# INKTIME_SCHEMA.net
KiCad netlist of a schematic drawn in EAGLE
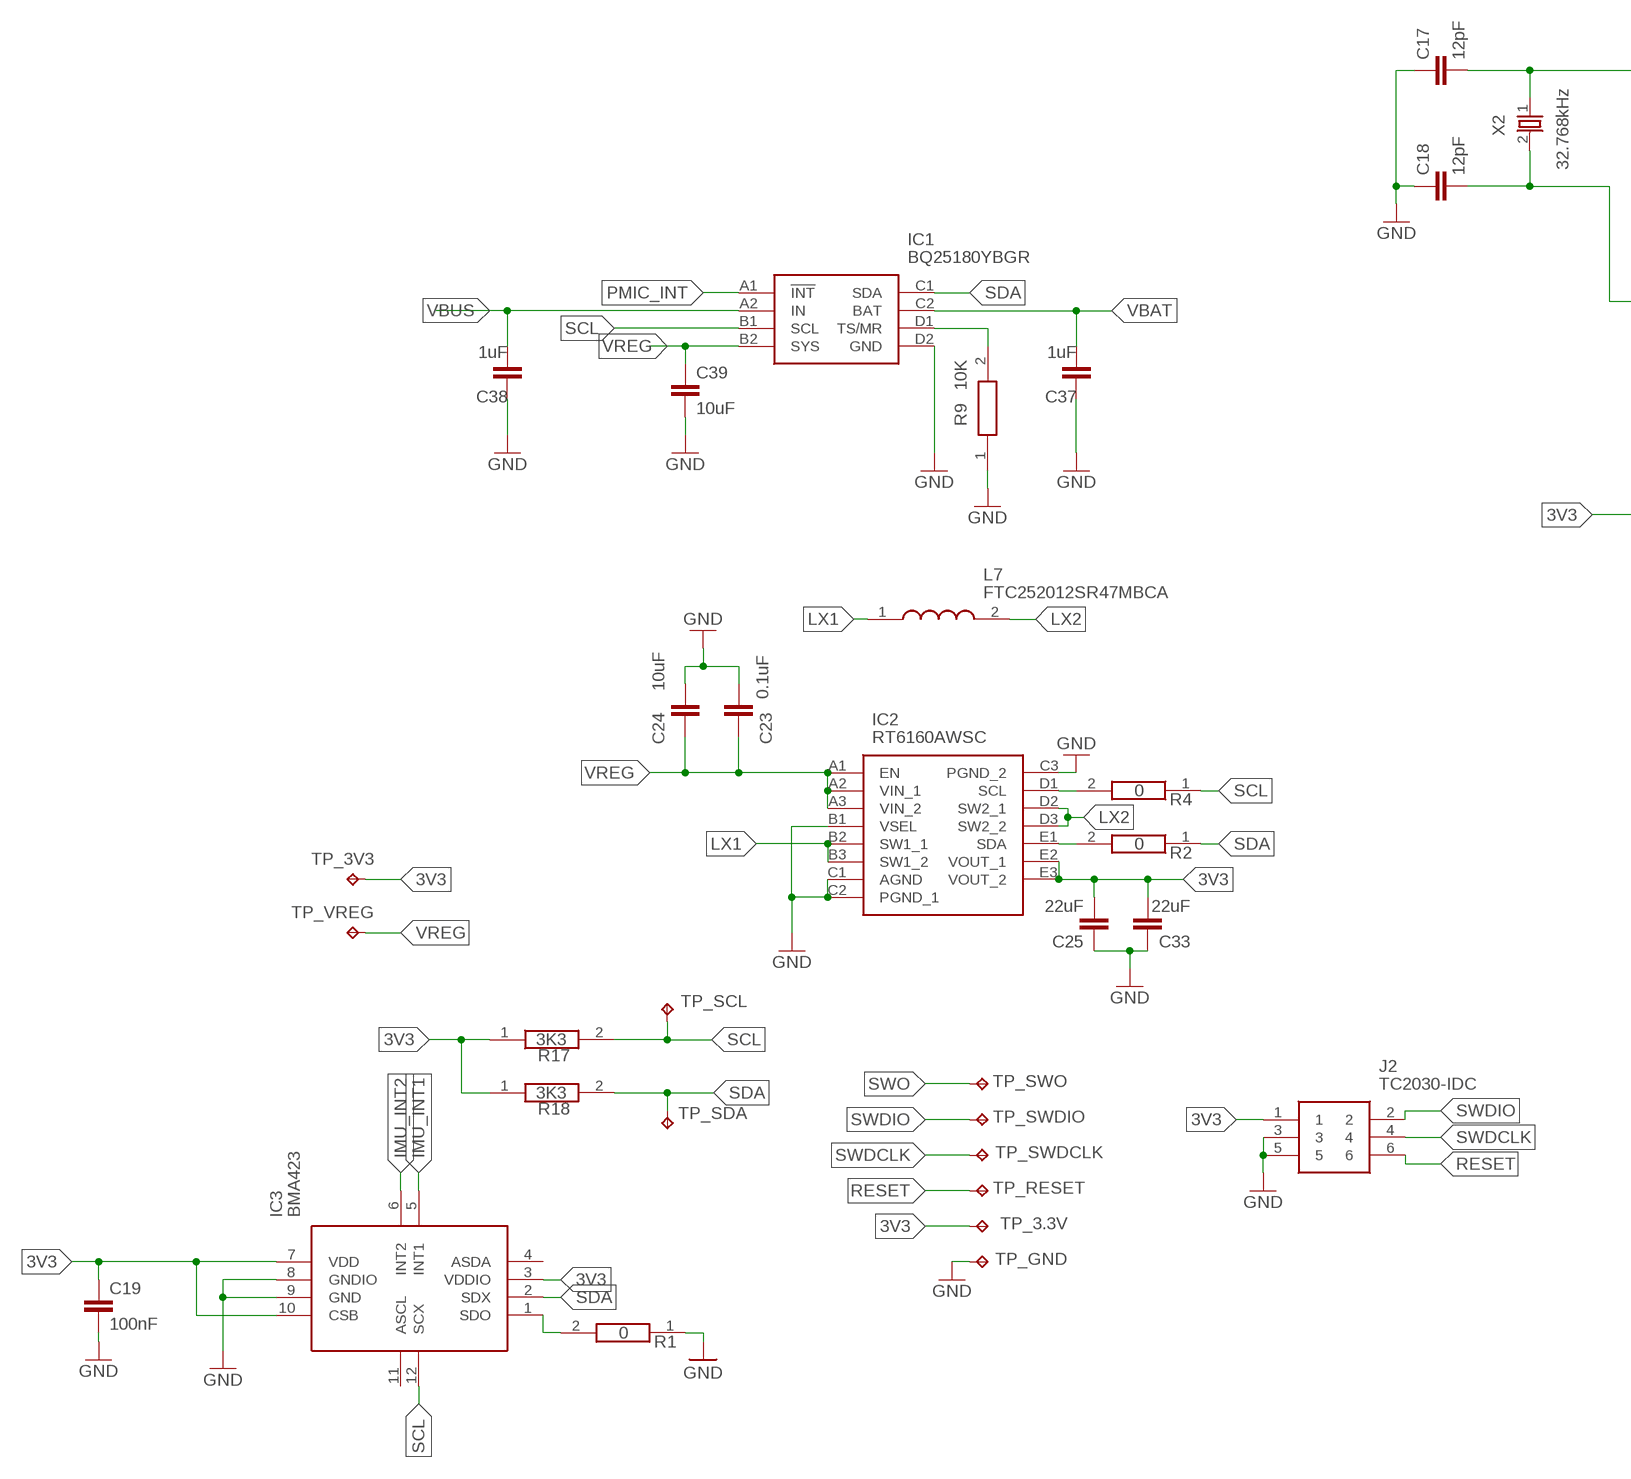
[diagram p0: schematic, sheet 1, part 1 of 2]
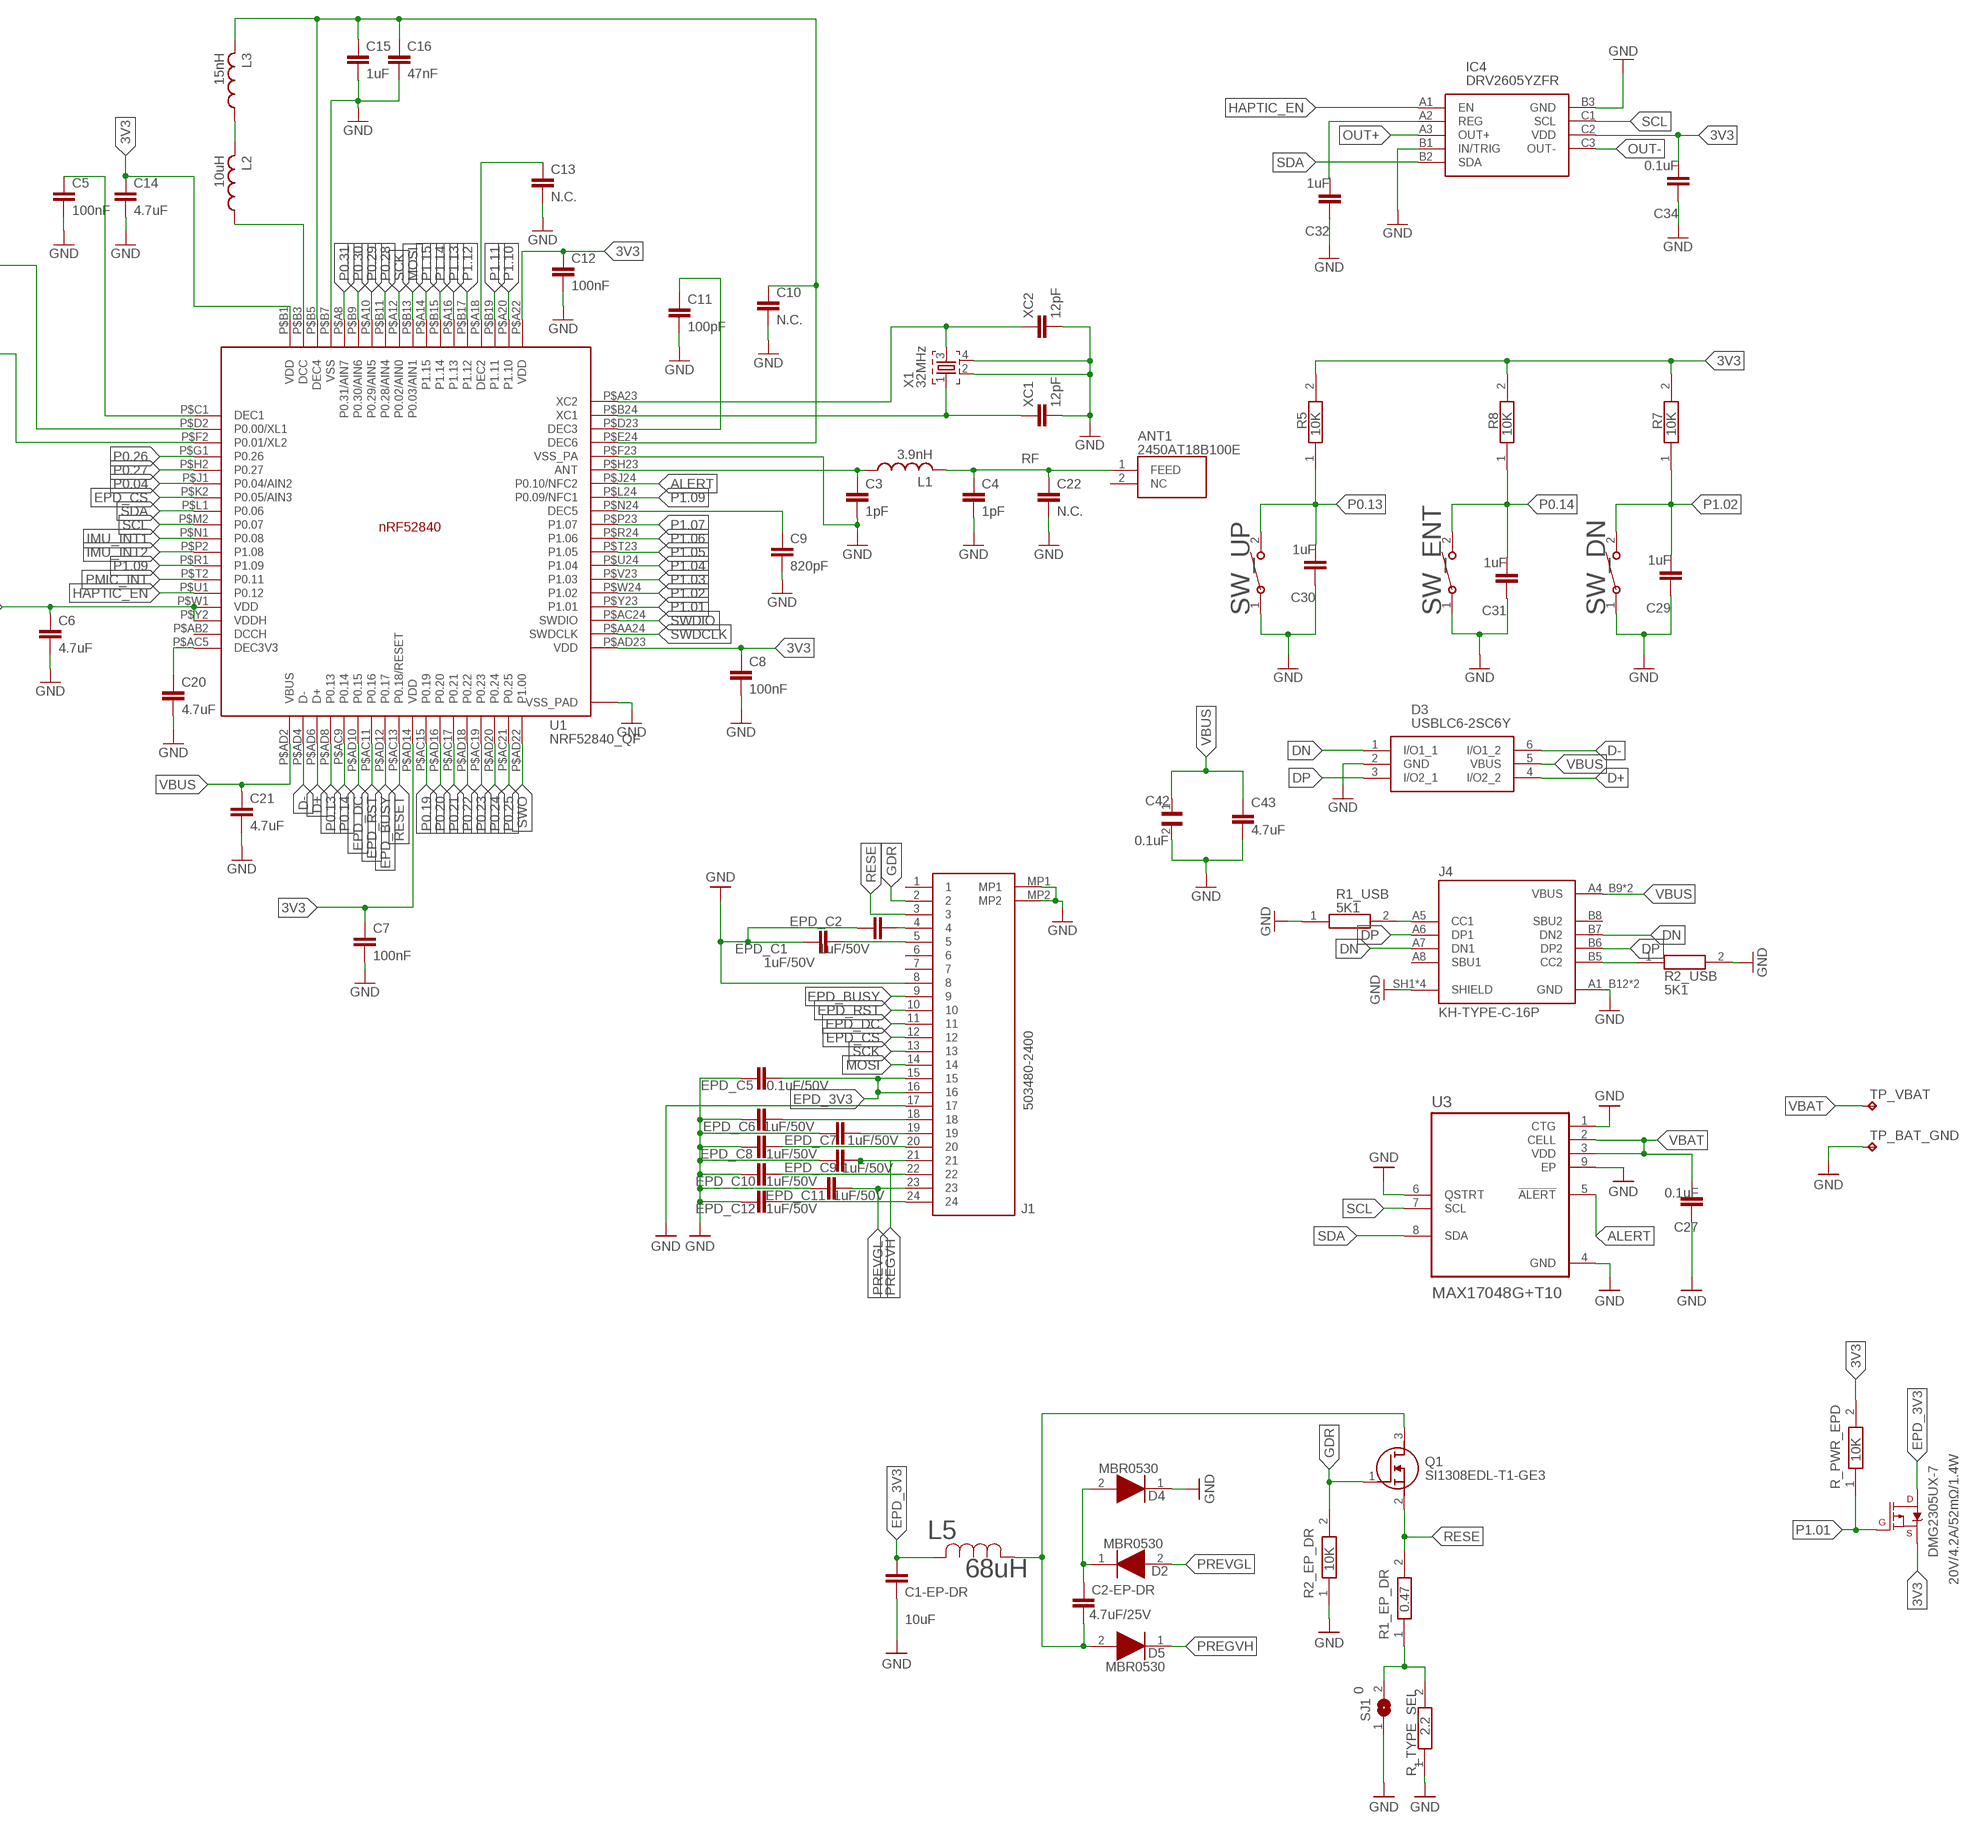
[diagram p1: schematic, sheet 1, part 2 of 2]

(export (version "E")
  (design (tool "Eeschema 10.0.6"))
  (components
    (comp (ref "ANT1")
      (value "2450AT18B100E")
      (footprint "eagle-import:2450AT18B100E_ANTC3216X140N")
      (fields (field (name "MOUSER_PART_NUMBER") "609-2450AT18B100E"))
      (libsource (lib "eagle-import") (part "2450AT18B100E_2450AT18B100E"))
    )
    (comp (ref "C1-EP-DR")
      (value "10uF")
      (footprint "eagle-import:NORDIC_NRF_3_RESC0402_L")
      (libsource (lib "eagle-import") (part "NORDIC_NRF_3_CAPACITOR_0402_L"))
    )
    (comp (ref "C2-EP-DR")
      (value "4.7uF/25V")
      (footprint "eagle-import:NORDIC_NRF_3_RESC0402_L")
      (libsource (lib "eagle-import") (part "NORDIC_NRF_3_CAPACITOR_0402_L"))
    )
    (comp (ref "C3")
      (value "1pF")
      (footprint "eagle-import:NORDIC_NRF_3_RESC0201_L")
      (libsource (lib "eagle-import") (part "NORDIC_NRF_3_CAPACITOR_0201_L"))
    )
    (comp (ref "C4")
      (value "1pF")
      (footprint "eagle-import:NORDIC_NRF_3_RESC0201_L")
      (libsource (lib "eagle-import") (part "NORDIC_NRF_3_CAPACITOR_0201_L"))
    )
    (comp (ref "C5")
      (value "100nF")
      (footprint "eagle-import:NORDIC_NRF_3_RESC0201_L")
      (libsource (lib "eagle-import") (part "NORDIC_NRF_3_CAPACITOR_0201_L"))
    )
    (comp (ref "C6")
      (value "4.7uF")
      (footprint "eagle-import:PERFECT_0402_0402")
      (libsource (lib "eagle-import") (part "PERFECT_0402_CAP_0402"))
    )
    (comp (ref "C7")
      (value "100nF")
      (footprint "eagle-import:NORDIC_NRF_3_RESC0201_L")
      (libsource (lib "eagle-import") (part "NORDIC_NRF_3_CAPACITOR_0201_L"))
    )
    (comp (ref "C8")
      (value "100nF")
      (footprint "eagle-import:NORDIC_NRF_3_RESC0201_L")
      (libsource (lib "eagle-import") (part "NORDIC_NRF_3_CAPACITOR_0201_L"))
    )
    (comp (ref "C9")
      (value "820pF")
      (footprint "eagle-import:NORDIC_NRF_3_RESC0201_L")
      (libsource (lib "eagle-import") (part "NORDIC_NRF_3_CAPACITOR_0201_L"))
    )
    (comp (ref "C10")
      (value "N.C.")
      (footprint "eagle-import:NORDIC_NRF_3_RESC0201_L")
      (libsource (lib "eagle-import") (part "NORDIC_NRF_3_CAPACITOR_0201_L"))
    )
    (comp (ref "C11")
      (value "100pF")
      (footprint "eagle-import:NORDIC_NRF_3_RESC0201_L")
      (libsource (lib "eagle-import") (part "NORDIC_NRF_3_CAPACITOR_0201_L"))
    )
    (comp (ref "C12")
      (value "100nF")
      (footprint "eagle-import:NORDIC_NRF_3_RESC0201_L")
      (libsource (lib "eagle-import") (part "NORDIC_NRF_3_CAPACITOR_0201_L"))
    )
    (comp (ref "C13")
      (value "N.C.")
      (footprint "eagle-import:NORDIC_NRF_3_RESC0201_L")
      (libsource (lib "eagle-import") (part "NORDIC_NRF_3_CAPACITOR_0201_L"))
    )
    (comp (ref "C14")
      (value "4.7uF")
      (footprint "eagle-import:PERFECT_0402_0402")
      (libsource (lib "eagle-import") (part "PERFECT_0402_CAP_0402"))
    )
    (comp (ref "C15")
      (value "1uF")
      (footprint "eagle-import:NORDIC_NRF_3_RESC0402_L")
      (libsource (lib "eagle-import") (part "NORDIC_NRF_3_CAPACITOR_0402_L"))
    )
    (comp (ref "C16")
      (value "47nF")
      (footprint "eagle-import:PERFECT_0402_0402")
      (libsource (lib "eagle-import") (part "PERFECT_0402_CAP_0402"))
    )
    (comp (ref "C17")
      (value "12pF")
      (footprint "eagle-import:NORDIC_NRF_3_RESC0201_L")
      (libsource (lib "eagle-import") (part "NORDIC_NRF_3_CAPACITOR_0201_L"))
    )
    (comp (ref "C18")
      (value "12pF")
      (footprint "eagle-import:NORDIC_NRF_3_RESC0201_L")
      (libsource (lib "eagle-import") (part "NORDIC_NRF_3_CAPACITOR_0201_L"))
    )
    (comp (ref "C19")
      (value "100nF")
      (footprint "eagle-import:NORDIC_NRF_3_RESC0201_L")
      (libsource (lib "eagle-import") (part "NORDIC_NRF_3_CAPACITOR_0201_L"))
    )
    (comp (ref "C20")
      (value "4.7uF")
      (footprint "eagle-import:PERFECT_0402_0402")
      (libsource (lib "eagle-import") (part "PERFECT_0402_CAP_0402"))
    )
    (comp (ref "C21")
      (value "4.7uF")
      (footprint "eagle-import:PERFECT_0402_0402")
      (libsource (lib "eagle-import") (part "PERFECT_0402_CAP_0402"))
    )
    (comp (ref "C22")
      (value "N.C.")
      (footprint "eagle-import:NORDIC_NRF_3_RESC0201_L")
      (libsource (lib "eagle-import") (part "NORDIC_NRF_3_CAPACITOR_0201_L"))
    )
    (comp (ref "C23")
      (value "0.1uF")
      (footprint "eagle-import:NORDIC_NRF_3_RESC0201_L")
      (libsource (lib "eagle-import") (part "NORDIC_NRF_3_CAPACITOR_0201_L"))
    )
    (comp (ref "C24")
      (value "10uF")
      (footprint "eagle-import:NORDIC_NRF_3_RESC0402_N")
      (libsource (lib "eagle-import") (part "NORDIC_NRF_3_CAPACITOR_0402_N"))
    )
    (comp (ref "C25")
      (value "22uF")
      (footprint "eagle-import:NORDIC_NRF_3_RESC0402_N")
      (libsource (lib "eagle-import") (part "NORDIC_NRF_3_CAPACITOR_0402_N"))
    )
    (comp (ref "C27")
      (value "0.1uF")
      (footprint "eagle-import:NORDIC_NRF_3_RESC0201_L")
      (libsource (lib "eagle-import") (part "NORDIC_NRF_3_CAPACITOR_0201_L"))
    )
    (comp (ref "C29")
      (value "1uF")
      (footprint "eagle-import:NORDIC_NRF_3_RESC0402_L")
      (libsource (lib "eagle-import") (part "NORDIC_NRF_3_CAPACITOR_0402_L"))
    )
    (comp (ref "C30")
      (value "1uF")
      (footprint "eagle-import:NORDIC_NRF_3_RESC0402_L")
      (libsource (lib "eagle-import") (part "NORDIC_NRF_3_CAPACITOR_0402_L"))
    )
    (comp (ref "C31")
      (value "1uF")
      (footprint "eagle-import:NORDIC_NRF_3_RESC0402_L")
      (libsource (lib "eagle-import") (part "NORDIC_NRF_3_CAPACITOR_0402_L"))
    )
    (comp (ref "C32")
      (value "1uF")
      (footprint "eagle-import:NORDIC_NRF_3_RESC0402_L")
      (libsource (lib "eagle-import") (part "NORDIC_NRF_3_CAPACITOR_0402_L"))
    )
    (comp (ref "C33")
      (value "22uF")
      (footprint "eagle-import:NORDIC_NRF_3_RESC0402_N")
      (libsource (lib "eagle-import") (part "NORDIC_NRF_3_CAPACITOR_0402_N"))
    )
    (comp (ref "C34")
      (value "0.1uF")
      (footprint "eagle-import:NORDIC_NRF_3_RESC0201_L")
      (libsource (lib "eagle-import") (part "NORDIC_NRF_3_CAPACITOR_0201_L"))
    )
    (comp (ref "C37")
      (value "1uF")
      (footprint "eagle-import:NORDIC_NRF_3_RESC0402_N")
      (libsource (lib "eagle-import") (part "NORDIC_NRF_3_CAPACITOR_0402_N"))
    )
    (comp (ref "C38")
      (value "1uF")
      (footprint "eagle-import:NORDIC_NRF_3_RESC0402_N")
      (libsource (lib "eagle-import") (part "NORDIC_NRF_3_CAPACITOR_0402_N"))
    )
    (comp (ref "C39")
      (value "10uF")
      (footprint "eagle-import:PERFECT_0402_0402")
      (libsource (lib "eagle-import") (part "PERFECT_0402_CAP_0402"))
    )
    (comp (ref "C42")
      (value "0.1uF")
      (footprint "eagle-import:GRM011R60J152KE01L_1_0201")
      (libsource (lib "eagle-import") (part "GRM011R60J152KE01L_1_GRM011R60J152KE01L"))
    )
    (comp (ref "C43")
      (value "4.7uF")
      (footprint "eagle-import:NORDIC_NRF_3_RESC0603_N")
      (libsource (lib "eagle-import") (part "NORDIC_NRF_3_CAPACITOR_0603_N"))
    )
    (comp (ref "D2")
      (value "MBR0530")
      (footprint "eagle-import:ESP32_C6_LIBRARY_5_SOD3716X135N")
      (fields (field (name "MF") "ON Semiconductor"))
      (libsource (lib "eagle-import") (part "ESP32_C6_LIBRARY_5_MBR0530"))
    )
    (comp (ref "D3")
      (value "USBLC6-2SC6Y")
      (footprint "eagle-import:ESP32_C6_LIBRARY_3_SOT95P280X145-6N")
      (fields (field (name "MF") "STMicroelectronics"))
      (libsource (lib "eagle-import") (part "ESP32_C6_LIBRARY_3_USBLC6-2SC6Y"))
    )
    (comp (ref "D4")
      (value "MBR0530")
      (footprint "eagle-import:ESP32_C6_LIBRARY_5_SOD3716X135N")
      (fields (field (name "MF") "ON Semiconductor"))
      (libsource (lib "eagle-import") (part "ESP32_C6_LIBRARY_5_MBR0530"))
    )
    (comp (ref "D5")
      (value "MBR0530")
      (footprint "eagle-import:ESP32_C6_LIBRARY_5_SOD3716X135N")
      (fields (field (name "MF") "ON Semiconductor"))
      (libsource (lib "eagle-import") (part "ESP32_C6_LIBRARY_5_MBR0530"))
    )
    (comp (ref "DMG2305UX-7")
      (value "20V/4.2A/52mΩ/1.4W")
      (footprint "eagle-import:ESP32_C6_LIBRARY_4_ESP32_C6_LIBRARY_4_ESP32_C6_LIBRARY_4_ESP32_C6_LIBRARY_4_ESP32_WROVER_SPARKFUN-DISCRETESEMI_SOT23-3")
      (libsource (lib "eagle-import") (part "ESP32_C6_LIBRARY_4_ESP32_WROVER_SPARKFUN-DISCRETESEMI_MOSFET_PCH-DMG2305UX-7"))
    )
    (comp (ref "EPD_C1")
      (value "1uF/50V")
      (footprint "eagle-import:NORDIC_NRF_3_RESC0402_L")
      (libsource (lib "eagle-import") (part "NORDIC_NRF_3_CAPACITOR_0402_L"))
    )
    (comp (ref "EPD_C2")
      (value "1uF/50V")
      (footprint "eagle-import:NORDIC_NRF_3_RESC0402_L")
      (libsource (lib "eagle-import") (part "NORDIC_NRF_3_CAPACITOR_0402_L"))
    )
    (comp (ref "EPD_C5")
      (value "0.1uF/50V")
      (footprint "eagle-import:NORDIC_NRF_3_RESC0201_L")
      (libsource (lib "eagle-import") (part "NORDIC_NRF_3_CAPACITOR_0201_L"))
    )
    (comp (ref "EPD_C6")
      (value "1uF/50V")
      (footprint "eagle-import:NORDIC_NRF_3_RESC0402_L")
      (libsource (lib "eagle-import") (part "NORDIC_NRF_3_CAPACITOR_0402_L"))
    )
    (comp (ref "EPD_C7")
      (value "1uF/50V")
      (footprint "eagle-import:NORDIC_NRF_3_RESC0402_L")
      (libsource (lib "eagle-import") (part "NORDIC_NRF_3_CAPACITOR_0402_L"))
    )
    (comp (ref "EPD_C8")
      (value "1uF/50V")
      (footprint "eagle-import:NORDIC_NRF_3_RESC0402_L")
      (libsource (lib "eagle-import") (part "NORDIC_NRF_3_CAPACITOR_0402_L"))
    )
    (comp (ref "EPD_C9")
      (value "1uF/50V")
      (footprint "eagle-import:NORDIC_NRF_3_RESC0402_L")
      (libsource (lib "eagle-import") (part "NORDIC_NRF_3_CAPACITOR_0402_L"))
    )
    (comp (ref "EPD_C10")
      (value "1uF/50V")
      (footprint "eagle-import:NORDIC_NRF_3_RESC0402_L")
      (libsource (lib "eagle-import") (part "NORDIC_NRF_3_CAPACITOR_0402_L"))
    )
    (comp (ref "EPD_C11")
      (value "1uF/50V")
      (footprint "eagle-import:NORDIC_NRF_3_RESC0402_L")
      (libsource (lib "eagle-import") (part "NORDIC_NRF_3_CAPACITOR_0402_L"))
    )
    (comp (ref "EPD_C12")
      (value "1uF/50V")
      (footprint "eagle-import:NORDIC_NRF_3_RESC0402_L")
      (libsource (lib "eagle-import") (part "NORDIC_NRF_3_CAPACITOR_0402_L"))
    )
    (comp (ref "IC1")
      (value "BQ25180YBGR")
      (footprint "eagle-import:BQ25180YBGR_BGA8C40P2X4_100X155X50")
      (fields (field (name "MOUSER_PART_NUMBER") "595-BQ25180YBGR"))
      (libsource (lib "eagle-import") (part "BQ25180YBGR_BQ25180YBGR"))
    )
    (comp (ref "IC2")
      (value "RT6160AWSC")
      (footprint "eagle-import:RT6160AWSC_BGA15C40P3X5_140X230X60")
      (fields (field (name "MOUSER_PART_NUMBER") "835-RT6160AWSC"))
      (libsource (lib "eagle-import") (part "RT6160AWSC_RT6160AWSC"))
    )
    (comp (ref "IC3")
      (value "BMA423")
      (footprint "eagle-import:BMA423_BMA423")
      (fields (field (name "MOUSER_PART_NUMBER") "262-BMA423"))
      (libsource (lib "eagle-import") (part "BMA423_BMA423"))
    )
    (comp (ref "IC4")
      (value "DRV2605YZFR")
      (footprint "eagle-import:DRV2605YZFR_BGA9C50P3X3_144X144X62")
      (libsource (lib "eagle-import") (part "DRV2605YZFR_DRV2605YZFR"))
    )
    (comp (ref "J1")
      (value "503480-2400")
      (footprint "eagle-import:503480-2400_5034802400")
      (fields (field (name "MOUSER_PART_NUMBER") "538-503480-2400"))
      (libsource (lib "eagle-import") (part "503480-2400_503480-2400"))
    )
    (comp (ref "J2")
      (value "TC2030-IDC")
      (footprint "eagle-import:TC2030-IDC_TC2030IDC")
      (libsource (lib "eagle-import") (part "TC2030-IDC_TC2030-IDC"))
    )
    (comp (ref "J4")
      (value "KH-TYPE-C-16P")
      (footprint "eagle-import:KH-TYPE-C-16P_KINGHELM_KH-TYPE-C-16P")
      (fields (field (name "MF") "kinghelm"))
      (libsource (lib "eagle-import") (part "KH-TYPE-C-16P_KH-TYPE-C-16P"))
    )
    (comp (ref "L1")
      (value "3.9nH")
      (footprint "eagle-import:NORDIC_NRF_2_RESC0201_L")
      (libsource (lib "eagle-import") (part "NORDIC_NRF_2_INDUCTOR_0201_L"))
    )
    (comp (ref "L2")
      (value "10uH")
      (footprint "eagle-import:NORDIC_NRF_2_RESC0201_L")
      (libsource (lib "eagle-import") (part "NORDIC_NRF_2_INDUCTOR_0201_L"))
    )
    (comp (ref "L3")
      (value "15nH")
      (footprint "eagle-import:NORDIC_NRF_2_RESC0201_L")
      (libsource (lib "eagle-import") (part "NORDIC_NRF_2_INDUCTOR_0201_L"))
    )
    (comp (ref "L5")
      (value "68uH")
      (footprint "eagle-import:ESP32_C6_LIBRARY_2_IND_4828-WE-TPC_WRE")
      (fields
        (field (name "MANUFACTURER_PART_NUMBER") "744043680")
        (field (name "COPYRIGHT") "Copyright (C) 2024 Ultra Librarian. All rights reserved.")
      )
      (libsource (lib "eagle-import") (part "ESP32_C6_LIBRARY_2_744043680IND_4828-WE-TPC_WRE"))
    )
    (comp (ref "L7")
      (value "FTC252012SR47MBCA")
      (footprint "eagle-import:MLP2016SR47MT0S1_INDC2016X100N")
      (libsource (lib "eagle-import") (part "MLP2016SR47MT0S1_FTC252012SR47MBCA"))
    )
    (comp (ref "Q1")
      (value "SI1308EDL-T1-GE3")
      (footprint "eagle-import:ESP32_C6_LIBRARY_6_SOT65P210X110-3N")
      (fields (field (name "MF") "Vishay Siliconix"))
      (libsource (lib "eagle-import") (part "ESP32_C6_LIBRARY_6_SI1308EDL-T1-GE3"))
    )
    (comp (ref "R1")
      (value "0")
      (footprint "eagle-import:CPF0201D7K68C1_0201")
      (libsource (lib "eagle-import") (part "CPF0201D7K68C1_CPF0201D7K68C1"))
    )
    (comp (ref "R1_EP_DR")
      (value "0.47")
      (footprint "eagle-import:CPF0201D7K68C1_0201")
      (libsource (lib "eagle-import") (part "CPF0201D7K68C1_CPF0201D7K68C1"))
    )
    (comp (ref "R1_USB")
      (value "5K1")
      (footprint "eagle-import:CPF0201D7K68C1_0201")
      (libsource (lib "eagle-import") (part "CPF0201D7K68C1_CPF0201D7K68C1"))
    )
    (comp (ref "R2")
      (value "0")
      (footprint "eagle-import:CPF0201D7K68C1_0201")
      (libsource (lib "eagle-import") (part "CPF0201D7K68C1_CPF0201D7K68C1"))
    )
    (comp (ref "R2_EP_DR")
      (value "10K")
      (footprint "eagle-import:CPF0201D7K68C1_0201")
      (libsource (lib "eagle-import") (part "CPF0201D7K68C1_CPF0201D7K68C1"))
    )
    (comp (ref "R2_USB")
      (value "5K1")
      (footprint "eagle-import:CPF0201D7K68C1_0201")
      (libsource (lib "eagle-import") (part "CPF0201D7K68C1_CPF0201D7K68C1"))
    )
    (comp (ref "R4")
      (value "0")
      (footprint "eagle-import:CPF0201D7K68C1_0201")
      (libsource (lib "eagle-import") (part "CPF0201D7K68C1_CPF0201D7K68C1"))
    )
    (comp (ref "R5")
      (value "10K")
      (footprint "eagle-import:CPF0201D7K68C1_0201")
      (libsource (lib "eagle-import") (part "CPF0201D7K68C1_CPF0201D7K68C1"))
    )
    (comp (ref "R7")
      (value "10K")
      (footprint "eagle-import:CPF0201D7K68C1_0201")
      (libsource (lib "eagle-import") (part "CPF0201D7K68C1_CPF0201D7K68C1"))
    )
    (comp (ref "R8")
      (value "10K")
      (footprint "eagle-import:CPF0201D7K68C1_0201")
      (libsource (lib "eagle-import") (part "CPF0201D7K68C1_CPF0201D7K68C1"))
    )
    (comp (ref "R9")
      (value "10K")
      (footprint "eagle-import:CPF0201D7K68C1_0201")
      (libsource (lib "eagle-import") (part "CPF0201D7K68C1_CPF0201D7K68C1"))
    )
    (comp (ref "R17")
      (value "3K3")
      (footprint "eagle-import:CPF0201D7K68C1_0201")
      (libsource (lib "eagle-import") (part "CPF0201D7K68C1_CPF0201D7K68C1"))
    )
    (comp (ref "R18")
      (value "3K3")
      (footprint "eagle-import:CPF0201D7K68C1_0201")
      (libsource (lib "eagle-import") (part "CPF0201D7K68C1_CPF0201D7K68C1"))
    )
    (comp (ref "R_PWR_EPD")
      (value "10K")
      (footprint "eagle-import:CPF0201D7K68C1_0201")
      (libsource (lib "eagle-import") (part "CPF0201D7K68C1_CPF0201D7K68C1"))
    )
    (comp (ref "R_TYPE_SEL")
      (value "2.2")
      (footprint "eagle-import:CPF0201D7K68C1_0201")
      (libsource (lib "eagle-import") (part "CPF0201D7K68C1_CPF0201D7K68C1"))
    )
    (comp (ref "SJ1")
      (value "0")
      (footprint "eagle-import:ESP32_C6_LIBRARY_7_JUMPER_SJ")
      (libsource (lib "eagle-import") (part "ESP32_C6_LIBRARY_7_JUMPER_SJ"))
    )
    (comp (ref "SW_DN")
      (value "2025-10-22_07-23-44_LIBRARY_EVP-AKE31ASW_EVP-AKE31A_PAN")
      (footprint "eagle-import:2025-10-22_07-23-44_LIBRARY_SW_EVP-AKE31A_PAN")
      (fields
        (field (name "MANUFACTURER_PART_NUMBER") "EVP-AKE31A")
        (field (name "COPYRIGHT") "Copyright (C) 2025 Ultra Librarian. All rights reserved.")
      )
      (libsource (lib "eagle-import") (part "2025-10-22_07-23-44_LIBRARY_EVP-AKE31ASW_EVP-AKE31A_PAN"))
    )
    (comp (ref "SW_ENT")
      (value "2025-10-22_07-23-44_LIBRARY_EVP-AKE31ASW_EVP-AKE31A_PAN")
      (footprint "eagle-import:2025-10-22_07-23-44_LIBRARY_SW_EVP-AKE31A_PAN")
      (fields
        (field (name "MANUFACTURER_PART_NUMBER") "EVP-AKE31A")
        (field (name "COPYRIGHT") "Copyright (C) 2025 Ultra Librarian. All rights reserved.")
      )
      (libsource (lib "eagle-import") (part "2025-10-22_07-23-44_LIBRARY_EVP-AKE31ASW_EVP-AKE31A_PAN"))
    )
    (comp (ref "SW_UP")
      (value "2025-10-22_07-23-44_LIBRARY_EVP-AKE31ASW_EVP-AKE31A_PAN")
      (footprint "eagle-import:2025-10-22_07-23-44_LIBRARY_SW_EVP-AKE31A_PAN")
      (fields
        (field (name "MANUFACTURER_PART_NUMBER") "EVP-AKE31A")
        (field (name "COPYRIGHT") "Copyright (C) 2025 Ultra Librarian. All rights reserved.")
      )
      (libsource (lib "eagle-import") (part "2025-10-22_07-23-44_LIBRARY_EVP-AKE31ASW_EVP-AKE31A_PAN"))
    )
    (comp (ref "TP_3.3V")
      (value "HECTOR_WATCH_1_TPTP20R")
      (footprint "eagle-import:HECTOR_WATCH_1_TP20R")
      (libsource (lib "eagle-import") (part "HECTOR_WATCH_1_TPTP20R"))
    )
    (comp (ref "TP_3V3")
      (value "HECTOR_WATCH_1_TPTP20R")
      (footprint "eagle-import:HECTOR_WATCH_1_TP20R")
      (libsource (lib "eagle-import") (part "HECTOR_WATCH_1_TPTP20R"))
    )
    (comp (ref "TP_BAT_GND")
      (value "HECTOR_WATCH_1_TPTP20R")
      (footprint "eagle-import:HECTOR_WATCH_1_TP20R")
      (libsource (lib "eagle-import") (part "HECTOR_WATCH_1_TPTP20R"))
    )
    (comp (ref "TP_GND")
      (value "HECTOR_WATCH_1_TPTP20R")
      (footprint "eagle-import:HECTOR_WATCH_1_TP20R")
      (libsource (lib "eagle-import") (part "HECTOR_WATCH_1_TPTP20R"))
    )
    (comp (ref "TP_RESET")
      (value "HECTOR_WATCH_1_TPTP20R")
      (footprint "eagle-import:HECTOR_WATCH_1_TP20R")
      (libsource (lib "eagle-import") (part "HECTOR_WATCH_1_TPTP20R"))
    )
    (comp (ref "TP_SCL")
      (value "HECTOR_WATCH_1_TPTP20R")
      (footprint "eagle-import:HECTOR_WATCH_1_TP20R")
      (libsource (lib "eagle-import") (part "HECTOR_WATCH_1_TPTP20R"))
    )
    (comp (ref "TP_SDA")
      (value "HECTOR_WATCH_1_TPTP20R")
      (footprint "eagle-import:HECTOR_WATCH_1_TP20R")
      (libsource (lib "eagle-import") (part "HECTOR_WATCH_1_TPTP20R"))
    )
    (comp (ref "TP_SWDCLK")
      (value "HECTOR_WATCH_1_TPTP20R")
      (footprint "eagle-import:HECTOR_WATCH_1_TP20R")
      (libsource (lib "eagle-import") (part "HECTOR_WATCH_1_TPTP20R"))
    )
    (comp (ref "TP_SWDIO")
      (value "HECTOR_WATCH_1_TPTP20R")
      (footprint "eagle-import:HECTOR_WATCH_1_TP20R")
      (libsource (lib "eagle-import") (part "HECTOR_WATCH_1_TPTP20R"))
    )
    (comp (ref "TP_SWO")
      (value "HECTOR_WATCH_1_TPTP20R")
      (footprint "eagle-import:HECTOR_WATCH_1_TP20R")
      (libsource (lib "eagle-import") (part "HECTOR_WATCH_1_TPTP20R"))
    )
    (comp (ref "TP_VBAT")
      (value "HECTOR_WATCH_1_TPTP20R")
      (footprint "eagle-import:HECTOR_WATCH_1_TP20R")
      (libsource (lib "eagle-import") (part "HECTOR_WATCH_1_TPTP20R"))
    )
    (comp (ref "TP_VREG")
      (value "HECTOR_WATCH_1_TPTP20R")
      (footprint "eagle-import:HECTOR_WATCH_1_TP20R")
      (libsource (lib "eagle-import") (part "HECTOR_WATCH_1_TPTP20R"))
    )
    (comp (ref "U1")
      (value "NRF52840_QF")
      (footprint "eagle-import:NORDIC_NRF_4_AQFN50P700X700X85_HS-74N")
      (libsource (lib "eagle-import") (part "NORDIC_NRF_4_NRF52840_QF"))
    )
    (comp (ref "U3")
      (value "MAX17048G+T10")
      (footprint "eagle-import:ESP32_C6_LIBRARY_SON50P200X200X80-9N")
      (fields (field (name "MF") "Analog Devices"))
      (libsource (lib "eagle-import") (part "ESP32_C6_LIBRARY_MAX17048G+T10"))
    )
    (comp (ref "X1")
      (value "32MHz")
      (footprint "eagle-import:NORDIC_NRF_BT-XTAL_2016_N")
      (libsource (lib "eagle-import") (part "NORDIC_NRF_XTAL_32MHZ"))
    )
    (comp (ref "X2")
      (value "32.768kHz")
      (footprint "eagle-import:NORDIC_NRF_1_XTAL_3215_N")
      (libsource (lib "eagle-import") (part "NORDIC_NRF_1_XTAL_32KHZ"))
    )
    (comp (ref "XC1")
      (value "12pF")
      (footprint "eagle-import:NORDIC_NRF_3_RESC0201_L")
      (libsource (lib "eagle-import") (part "NORDIC_NRF_3_CAPACITOR_0201_L"))
    )
    (comp (ref "XC2")
      (value "12pF")
      (footprint "eagle-import:NORDIC_NRF_3_RESC0201_L")
      (libsource (lib "eagle-import") (part "NORDIC_NRF_3_CAPACITOR_0201_L"))
    )
  )
  (nets
    (net (code "1") (name "/RF") (class "Default")
      (node (ref "ANT1") (pin "1") (pinfunction "FEED_1") (pintype "input"))
      (node (ref "C22") (pin "1") (pinfunction "1_1") (pintype "passive"))
      (node (ref "C4") (pin "1") (pinfunction "1_1") (pintype "passive"))
      (node (ref "L1") (pin "2") (pinfunction "2_2") (pintype "passive"))
    )
    (net (code "2") (name "3V3") (class "Default")
      (node (ref "C12") (pin "1") (pinfunction "1_1") (pintype "passive"))
      (node (ref "C14") (pin "1") (pinfunction "1_1") (pintype "passive"))
      (node (ref "C19") (pin "1") (pinfunction "1_1") (pintype "passive"))
      (node (ref "C25") (pin "1") (pinfunction "1_1") (pintype "passive"))
      (node (ref "C33") (pin "1") (pinfunction "1_1") (pintype "passive"))
      (node (ref "C34") (pin "2") (pinfunction "2_2") (pintype "passive"))
      (node (ref "C6") (pin "1") (pinfunction "1_1") (pintype "passive"))
      (node (ref "C7") (pin "1") (pinfunction "1_1") (pintype "passive"))
      (node (ref "C8") (pin "1") (pinfunction "1_1") (pintype "passive"))
      (node (ref "DMG2305UX-7") (pin "2") (pinfunction "S_2") (pintype "bidirectional"))
      (node (ref "IC2") (pin "E2") (pinfunction "VOUT_1_E2") (pintype "bidirectional"))
      (node (ref "IC2") (pin "E3") (pinfunction "VOUT_2_E3") (pintype "bidirectional"))
      (node (ref "IC3") (pin "10") (pinfunction "CSB_10") (pintype "bidirectional"))
      (node (ref "IC3") (pin "3") (pinfunction "VDDIO_3") (pintype "bidirectional"))
      (node (ref "IC3") (pin "7") (pinfunction "VDD_7") (pintype "bidirectional"))
      (node (ref "IC4") (pin "C2") (pinfunction "VDD_C2") (pintype "bidirectional"))
      (node (ref "J2") (pin "1") (pinfunction "1_1") (pintype "bidirectional"))
      (node (ref "R17") (pin "1") (pinfunction "1_1") (pintype "bidirectional"))
      (node (ref "R18") (pin "1") (pinfunction "1_1") (pintype "bidirectional"))
      (node (ref "R5") (pin "2") (pinfunction "2_2") (pintype "bidirectional"))
      (node (ref "R7") (pin "2") (pinfunction "2_2") (pintype "bidirectional"))
      (node (ref "R8") (pin "2") (pinfunction "2_2") (pintype "bidirectional"))
      (node (ref "R_PWR_EPD") (pin "2") (pinfunction "2_2") (pintype "bidirectional"))
      (node (ref "TP_3.3V") (pin "TP") (pinfunction "TP_TP") (pintype "input"))
      (node (ref "TP_3V3") (pin "TP") (pinfunction "TP_TP") (pintype "input"))
      (node (ref "U1") (pin "P$A22") (pinfunction "VDD_P$A22") (pintype "power_in"))
      (node (ref "U1") (pin "P$AD14") (pinfunction "VDD_P$AD14") (pintype "power_in"))
      (node (ref "U1") (pin "P$AD23") (pinfunction "VDD_P$AD23") (pintype "power_in"))
      (node (ref "U1") (pin "P$B1") (pinfunction "VDD_P$B1") (pintype "power_in"))
      (node (ref "U1") (pin "P$W1") (pinfunction "VDD_P$W1") (pintype "power_in"))
      (node (ref "U1") (pin "P$Y2") (pinfunction "VDDH_P$Y2") (pintype "power_in"))
    )
    (net (code "3") (name "ALERT") (class "Default")
      (node (ref "U1") (pin "P$J24") (pinfunction "P0.10/NFC2_P$J24") (pintype "bidirectional"))
      (node (ref "U3") (pin "5") (pinfunction "~{ALERT}_5") (pintype "output"))
    )
    (net (code "4") (name "D+") (class "Default")
      (node (ref "D3") (pin "4") (pinfunction "I/O2_2_4") (pintype "bidirectional"))
      (node (ref "U1") (pin "P$AD6") (pinfunction "D+_P$AD6") (pintype "bidirectional"))
    )
    (net (code "5") (name "D-") (class "Default")
      (node (ref "D3") (pin "6") (pinfunction "I/O1_2_6") (pintype "bidirectional"))
      (node (ref "U1") (pin "P$AD4") (pinfunction "D-_P$AD4") (pintype "bidirectional"))
    )
    (net (code "6") (name "DN") (class "Default")
      (node (ref "D3") (pin "1") (pinfunction "I/O1_1_1") (pintype "bidirectional"))
      (node (ref "J4") (pin "A7") (pinfunction "DN1_A7") (pintype "bidirectional"))
      (node (ref "J4") (pin "B7") (pinfunction "DN2_B7") (pintype "bidirectional"))
    )
    (net (code "7") (name "DP") (class "Default")
      (node (ref "D3") (pin "3") (pinfunction "I/O2_1_3") (pintype "bidirectional"))
      (node (ref "J4") (pin "A6") (pinfunction "DP1_A6") (pintype "bidirectional"))
      (node (ref "J4") (pin "B6") (pinfunction "DP2_B6") (pintype "bidirectional"))
    )
    (net (code "8") (name "EPD_3V3") (class "Default")
      (node (ref "C1-EP-DR") (pin "2") (pinfunction "2_2") (pintype "passive"))
      (node (ref "DMG2305UX-7") (pin "3") (pinfunction "D_3") (pintype "bidirectional"))
      (node (ref "EPD_C5") (pin "2") (pinfunction "2_2") (pintype "passive"))
      (node (ref "J1") (pin "15") (pinfunction "15_15") (pintype "bidirectional"))
      (node (ref "J1") (pin "16") (pinfunction "16_16") (pintype "bidirectional"))
      (node (ref "L5") (pin "2") (pinfunction "2_2") (pintype "passive"))
    )
    (net (code "9") (name "EPD_BUSY") (class "Default")
      (node (ref "J1") (pin "9") (pinfunction "9_9") (pintype "bidirectional"))
      (node (ref "U1") (pin "P$AD12") (pinfunction "P0.17_P$AD12") (pintype "bidirectional"))
    )
    (net (code "10") (name "EPD_CS") (class "Default")
      (node (ref "J1") (pin "12") (pinfunction "12_12") (pintype "bidirectional"))
      (node (ref "U1") (pin "P$K2") (pinfunction "P0.05/AIN3_P$K2") (pintype "bidirectional"))
    )
    (net (code "11") (name "EPD_DC") (class "Default")
      (node (ref "J1") (pin "11") (pinfunction "11_11") (pintype "bidirectional"))
      (node (ref "U1") (pin "P$AD10") (pinfunction "P0.15_P$AD10") (pintype "bidirectional"))
    )
    (net (code "12") (name "EPD_RST") (class "Default")
      (node (ref "J1") (pin "10") (pinfunction "10_10") (pintype "bidirectional"))
      (node (ref "U1") (pin "P$AC11") (pinfunction "P0.16_P$AC11") (pintype "bidirectional"))
    )
    (net (code "13") (name "GDR") (class "Default")
      (node (ref "J1") (pin "2") (pinfunction "2_2") (pintype "bidirectional"))
      (node (ref "Q1") (pin "1") (pinfunction "G_1") (pintype "bidirectional"))
      (node (ref "R2_EP_DR") (pin "2") (pinfunction "2_2") (pintype "bidirectional"))
    )
    (net (code "14") (name "GND") (class "Default")
      (node (ref "C1-EP-DR") (pin "1") (pinfunction "1_1") (pintype "passive"))
      (node (ref "C10") (pin "2") (pinfunction "2_2") (pintype "passive"))
      (node (ref "C11") (pin "2") (pinfunction "2_2") (pintype "passive"))
      (node (ref "C12") (pin "2") (pinfunction "2_2") (pintype "passive"))
      (node (ref "C13") (pin "2") (pinfunction "2_2") (pintype "passive"))
      (node (ref "C14") (pin "2") (pinfunction "2_2") (pintype "passive"))
      (node (ref "C15") (pin "2") (pinfunction "2_2") (pintype "passive"))
      (node (ref "C16") (pin "2") (pinfunction "2_2") (pintype "passive"))
      (node (ref "C17") (pin "1") (pinfunction "1_1") (pintype "passive"))
      (node (ref "C18") (pin "1") (pinfunction "1_1") (pintype "passive"))
      (node (ref "C19") (pin "2") (pinfunction "2_2") (pintype "passive"))
      (node (ref "C20") (pin "2") (pinfunction "2_2") (pintype "passive"))
      (node (ref "C21") (pin "2") (pinfunction "2_2") (pintype "passive"))
      (node (ref "C22") (pin "2") (pinfunction "2_2") (pintype "passive"))
      (node (ref "C23") (pin "1") (pinfunction "1_1") (pintype "passive"))
      (node (ref "C24") (pin "1") (pinfunction "1_1") (pintype "passive"))
      (node (ref "C25") (pin "2") (pinfunction "2_2") (pintype "passive"))
      (node (ref "C27") (pin "1") (pinfunction "1_1") (pintype "passive"))
      (node (ref "C29") (pin "1") (pinfunction "1_1") (pintype "passive"))
      (node (ref "C3") (pin "2") (pinfunction "2_2") (pintype "passive"))
      (node (ref "C30") (pin "1") (pinfunction "1_1") (pintype "passive"))
      (node (ref "C31") (pin "1") (pinfunction "1_1") (pintype "passive"))
      (node (ref "C32") (pin "1") (pinfunction "1_1") (pintype "passive"))
      (node (ref "C33") (pin "2") (pinfunction "2_2") (pintype "passive"))
      (node (ref "C34") (pin "1") (pinfunction "1_1") (pintype "passive"))
      (node (ref "C37") (pin "1") (pinfunction "1_1") (pintype "passive"))
      (node (ref "C38") (pin "1") (pinfunction "1_1") (pintype "passive"))
      (node (ref "C39") (pin "2") (pinfunction "2_2") (pintype "passive"))
      (node (ref "C4") (pin "2") (pinfunction "2_2") (pintype "passive"))
      (node (ref "C42") (pin "2") (pinfunction "2_2") (pintype "passive"))
      (node (ref "C43") (pin "2") (pinfunction "2_2") (pintype "passive"))
      (node (ref "C5") (pin "2") (pinfunction "2_2") (pintype "passive"))
      (node (ref "C6") (pin "2") (pinfunction "2_2") (pintype "passive"))
      (node (ref "C7") (pin "2") (pinfunction "2_2") (pintype "passive"))
      (node (ref "C8") (pin "2") (pinfunction "2_2") (pintype "passive"))
      (node (ref "C9") (pin "2") (pinfunction "2_2") (pintype "passive"))
      (node (ref "D3") (pin "2") (pinfunction "GND_2") (pintype "bidirectional"))
      (node (ref "D4") (pin "1") (pinfunction "K_1") (pintype "bidirectional"))
      (node (ref "EPD_C1") (pin "1") (pinfunction "1_1") (pintype "passive"))
      (node (ref "EPD_C10") (pin "1") (pinfunction "1_1") (pintype "passive"))
      (node (ref "EPD_C11") (pin "1") (pinfunction "1_1") (pintype "passive"))
      (node (ref "EPD_C12") (pin "1") (pinfunction "1_1") (pintype "passive"))
      (node (ref "EPD_C2") (pin "1") (pinfunction "1_1") (pintype "passive"))
      (node (ref "EPD_C5") (pin "1") (pinfunction "1_1") (pintype "passive"))
      (node (ref "EPD_C6") (pin "1") (pinfunction "1_1") (pintype "passive"))
      (node (ref "EPD_C7") (pin "1") (pinfunction "1_1") (pintype "passive"))
      (node (ref "EPD_C8") (pin "1") (pinfunction "1_1") (pintype "passive"))
      (node (ref "EPD_C9") (pin "1") (pinfunction "1_1") (pintype "passive"))
      (node (ref "IC1") (pin "D2") (pinfunction "GND_D2") (pintype "bidirectional"))
      (node (ref "IC2") (pin "B1") (pinfunction "VSEL_B1") (pintype "bidirectional"))
      (node (ref "IC2") (pin "C1") (pinfunction "AGND_C1") (pintype "bidirectional"))
      (node (ref "IC2") (pin "C2") (pinfunction "PGND_1_C2") (pintype "bidirectional"))
      (node (ref "IC2") (pin "C3") (pinfunction "PGND_2_C3") (pintype "bidirectional"))
      (node (ref "IC3") (pin "8") (pinfunction "GNDIO_8") (pintype "bidirectional"))
      (node (ref "IC3") (pin "9") (pinfunction "GND_9") (pintype "bidirectional"))
      (node (ref "IC4") (pin "B1") (pinfunction "IN/TRIG_B1") (pintype "bidirectional"))
      (node (ref "IC4") (pin "B3") (pinfunction "GND_B3") (pintype "bidirectional"))
      (node (ref "J1") (pin "17") (pinfunction "17_17") (pintype "bidirectional"))
      (node (ref "J1") (pin "8") (pinfunction "8_8") (pintype "bidirectional"))
      (node (ref "J1") (pin "MP1") (pinfunction "MP1_MP1") (pintype "bidirectional"))
      (node (ref "J1") (pin "MP2") (pinfunction "MP2_MP2") (pintype "bidirectional"))
      (node (ref "J2") (pin "3") (pinfunction "3_3") (pintype "bidirectional"))
      (node (ref "J2") (pin "5") (pinfunction "5_5") (pintype "bidirectional"))
      (node (ref "J4") (pin "A12_B1") (pinfunction "GND_A12_B1") (pintype "power_in"))
      (node (ref "J4") (pin "A1_B12") (pinfunction "GND_A1_B12") (pintype "power_in"))
      (node (ref "J4") (pin "SH1") (pinfunction "SHIELD_SH1") (pintype "passive"))
      (node (ref "J4") (pin "SH2") (pinfunction "SHIELD_SH2") (pintype "passive"))
      (node (ref "J4") (pin "SH3") (pinfunction "SHIELD_SH3") (pintype "passive"))
      (node (ref "J4") (pin "SH4") (pinfunction "SHIELD_SH4") (pintype "passive"))
      (node (ref "R1") (pin "1") (pinfunction "1_1") (pintype "bidirectional"))
      (node (ref "R1_USB") (pin "1") (pinfunction "1_1") (pintype "bidirectional"))
      (node (ref "R2_EP_DR") (pin "1") (pinfunction "1_1") (pintype "bidirectional"))
      (node (ref "R2_USB") (pin "2") (pinfunction "2_2") (pintype "bidirectional"))
      (node (ref "R9") (pin "1") (pinfunction "1_1") (pintype "bidirectional"))
      (node (ref "R_TYPE_SEL") (pin "1") (pinfunction "1_1") (pintype "bidirectional"))
      (node (ref "SJ1") (pin "1") (pinfunction "1_1") (pintype "passive"))
      (node (ref "SW_DN") (pin "1") (pinfunction "1_1") (pintype "passive"))
      (node (ref "SW_ENT") (pin "1") (pinfunction "1_1") (pintype "passive"))
      (node (ref "SW_UP") (pin "1") (pinfunction "1_1") (pintype "passive"))
      (node (ref "TP_BAT_GND") (pin "TP") (pinfunction "TP_TP") (pintype "input"))
      (node (ref "TP_GND") (pin "TP") (pinfunction "TP_TP") (pintype "input"))
      (node (ref "U1") (pin "P$74") (pinfunction "VSS_PAD_P$74") (pintype "bidirectional"))
      (node (ref "U1") (pin "P$75") (pinfunction "VSS_PAD_P$75") (pintype "bidirectional"))
      (node (ref "U1") (pin "P$76") (pinfunction "VSS_PAD_P$76") (pintype "bidirectional"))
      (node (ref "U1") (pin "P$77") (pinfunction "VSS_PAD_P$77") (pintype "bidirectional"))
      (node (ref "U1") (pin "P$78") (pinfunction "VSS_PAD_P$78") (pintype "bidirectional"))
      (node (ref "U1") (pin "P$79") (pinfunction "VSS_PAD_P$79") (pintype "bidirectional"))
      (node (ref "U1") (pin "P$80") (pinfunction "VSS_PAD_P$80") (pintype "bidirectional"))
      (node (ref "U1") (pin "P$81") (pinfunction "VSS_PAD_P$81") (pintype "bidirectional"))
      (node (ref "U1") (pin "P$82") (pinfunction "VSS_PAD_P$82") (pintype "bidirectional"))
      (node (ref "U1") (pin "P$83") (pinfunction "VSS_PAD_P$83") (pintype "bidirectional"))
      (node (ref "U1") (pin "P$84") (pinfunction "VSS_PAD_P$84") (pintype "bidirectional"))
      (node (ref "U1") (pin "P$85") (pinfunction "VSS_PAD_P$85") (pintype "bidirectional"))
      (node (ref "U1") (pin "P$86") (pinfunction "VSS_PAD_P$86") (pintype "bidirectional"))
      (node (ref "U1") (pin "P$87") (pinfunction "VSS_PAD_P$87") (pintype "bidirectional"))
      (node (ref "U1") (pin "P$88") (pinfunction "VSS_PAD_P$88") (pintype "bidirectional"))
      (node (ref "U1") (pin "P$89") (pinfunction "VSS_PAD_P$89") (pintype "bidirectional"))
      (node (ref "U1") (pin "P$90") (pinfunction "VSS_PAD_P$90") (pintype "bidirectional"))
      (node (ref "U1") (pin "P$B7") (pinfunction "VSS_P$B7") (pintype "power_in"))
      (node (ref "U1") (pin "P$F23") (pinfunction "VSS_PA_P$F23") (pintype "bidirectional"))
      (node (ref "U3") (pin "1") (pinfunction "CTG_1") (pintype "power_in"))
      (node (ref "U3") (pin "4") (pinfunction "GND_4") (pintype "power_in"))
      (node (ref "U3") (pin "6") (pinfunction "QSTRT_6") (pintype "input"))
      (node (ref "U3") (pin "9") (pinfunction "EP_9") (pintype "power_in"))
      (node (ref "X1") (pin "2") (pinfunction "2_2") (pintype "passive"))
      (node (ref "X1") (pin "4") (pinfunction "4_4") (pintype "passive"))
      (node (ref "XC1") (pin "2") (pinfunction "2_2") (pintype "passive"))
      (node (ref "XC2") (pin "2") (pinfunction "2_2") (pintype "passive"))
    )
    (net (code "15") (name "HAPTIC_EN") (class "Default")
      (node (ref "IC4") (pin "A1") (pinfunction "EN_A1") (pintype "bidirectional"))
      (node (ref "U1") (pin "P$U1") (pinfunction "P0.12_P$U1") (pintype "bidirectional"))
    )
    (net (code "16") (name "IMU_INT1") (class "Default")
      (node (ref "IC3") (pin "5") (pinfunction "INT1_5") (pintype "bidirectional"))
      (node (ref "U1") (pin "P$N1") (pinfunction "P0.08_P$N1") (pintype "bidirectional"))
    )
    (net (code "17") (name "IMU_INT2") (class "Default")
      (node (ref "IC3") (pin "6") (pinfunction "INT2_6") (pintype "bidirectional"))
      (node (ref "U1") (pin "P$P2") (pinfunction "P1.08_P$P2") (pintype "bidirectional"))
    )
    (net (code "18") (name "LX1") (class "Default")
      (node (ref "IC2") (pin "B2") (pinfunction "SW1_1_B2") (pintype "bidirectional"))
      (node (ref "IC2") (pin "B3") (pinfunction "SW1_2_B3") (pintype "bidirectional"))
      (node (ref "L7") (pin "1") (pinfunction "1_1") (pintype "bidirectional"))
    )
    (net (code "19") (name "LX2") (class "Default")
      (node (ref "IC2") (pin "D2") (pinfunction "SW2_1_D2") (pintype "bidirectional"))
      (node (ref "IC2") (pin "D3") (pinfunction "SW2_2_D3") (pintype "bidirectional"))
      (node (ref "L7") (pin "2") (pinfunction "2_2") (pintype "bidirectional"))
    )
    (net (code "20") (name "MOSI") (class "Default")
      (node (ref "J1") (pin "14") (pinfunction "14_14") (pintype "bidirectional"))
      (node (ref "U1") (pin "P$B13") (pinfunction "P0.03/AIN1_P$B13") (pintype "bidirectional"))
    )
    (net (code "21") (name "Net-(D2-K)") (class "Default")
      (node (ref "C2-EP-DR") (pin "2") (pinfunction "2_2") (pintype "passive"))
      (node (ref "D2") (pin "1") (pinfunction "K_1") (pintype "bidirectional"))
      (node (ref "D4") (pin "2") (pinfunction "A_2") (pintype "bidirectional"))
    )
    (net (code "22") (name "Net-(D5-A)") (class "Default")
      (node (ref "C2-EP-DR") (pin "1") (pinfunction "1_1") (pintype "passive"))
      (node (ref "D5") (pin "2") (pinfunction "A_2") (pintype "bidirectional"))
      (node (ref "L5") (pin "1") (pinfunction "1_1") (pintype "passive"))
      (node (ref "Q1") (pin "3") (pinfunction "D_3") (pintype "bidirectional"))
    )
    (net (code "23") (name "Net-(EPD_C1-Pad2)") (class "Default")
      (node (ref "EPD_C1") (pin "2") (pinfunction "2_2") (pintype "passive"))
      (node (ref "J1") (pin "5") (pinfunction "5_5") (pintype "bidirectional"))
    )
    (net (code "24") (name "Net-(EPD_C2-Pad2)") (class "Default")
      (node (ref "EPD_C2") (pin "2") (pinfunction "2_2") (pintype "passive"))
      (node (ref "J1") (pin "4") (pinfunction "4_4") (pintype "bidirectional"))
    )
    (net (code "25") (name "Net-(EPD_C6-Pad2)") (class "Default")
      (node (ref "EPD_C6") (pin "2") (pinfunction "2_2") (pintype "passive"))
      (node (ref "J1") (pin "18") (pinfunction "18_18") (pintype "bidirectional"))
    )
    (net (code "26") (name "Net-(EPD_C7-Pad2)") (class "Default")
      (node (ref "EPD_C7") (pin "2") (pinfunction "2_2") (pintype "passive"))
      (node (ref "J1") (pin "19") (pinfunction "19_19") (pintype "bidirectional"))
    )
    (net (code "27") (name "Net-(EPD_C8-Pad2)") (class "Default")
      (node (ref "EPD_C8") (pin "2") (pinfunction "2_2") (pintype "passive"))
      (node (ref "J1") (pin "20") (pinfunction "20_20") (pintype "bidirectional"))
    )
    (net (code "28") (name "Net-(EPD_C10-Pad2)") (class "Default")
      (node (ref "EPD_C10") (pin "2") (pinfunction "2_2") (pintype "passive"))
      (node (ref "J1") (pin "22") (pinfunction "22_22") (pintype "bidirectional"))
    )
    (net (code "29") (name "Net-(EPD_C12-Pad2)") (class "Default")
      (node (ref "EPD_C12") (pin "2") (pinfunction "2_2") (pintype "passive"))
      (node (ref "J1") (pin "24") (pinfunction "24_24") (pintype "bidirectional"))
    )
    (net (code "30") (name "Net-(IC1-TS{slash}MR)") (class "Default")
      (node (ref "IC1") (pin "D1") (pinfunction "TS/MR_D1") (pintype "bidirectional"))
      (node (ref "R9") (pin "2") (pinfunction "2_2") (pintype "bidirectional"))
    )
    (net (code "31") (name "Net-(IC2-SCL)") (class "Default")
      (node (ref "IC2") (pin "D1") (pinfunction "SCL_D1") (pintype "bidirectional"))
      (node (ref "R4") (pin "2") (pinfunction "2_2") (pintype "bidirectional"))
    )
    (net (code "32") (name "Net-(IC2-SDA)") (class "Default")
      (node (ref "IC2") (pin "E1") (pinfunction "SDA_E1") (pintype "bidirectional"))
      (node (ref "R2") (pin "2") (pinfunction "2_2") (pintype "bidirectional"))
    )
    (net (code "33") (name "Net-(IC3-SDO)") (class "Default")
      (node (ref "IC3") (pin "1") (pinfunction "SDO_1") (pintype "bidirectional"))
      (node (ref "R1") (pin "2") (pinfunction "2_2") (pintype "bidirectional"))
    )
    (net (code "34") (name "Net-(IC4-REG)") (class "Default")
      (node (ref "C32") (pin "2") (pinfunction "2_2") (pintype "passive"))
      (node (ref "IC4") (pin "A2") (pinfunction "REG_A2") (pintype "bidirectional"))
    )
    (net (code "35") (name "Net-(J4-CC1)") (class "Default")
      (node (ref "J4") (pin "A5") (pinfunction "CC1_A5") (pintype "bidirectional"))
      (node (ref "R1_USB") (pin "2") (pinfunction "2_2") (pintype "bidirectional"))
    )
    (net (code "36") (name "Net-(J4-CC2)") (class "Default")
      (node (ref "J4") (pin "B5") (pinfunction "CC2_B5") (pintype "bidirectional"))
      (node (ref "R2_USB") (pin "1") (pinfunction "1_1") (pintype "bidirectional"))
    )
    (net (code "37") (name "Net-(L2-Pad2)") (class "Default")
      (node (ref "L2") (pin "2") (pinfunction "2_2") (pintype "passive"))
      (node (ref "L3") (pin "1") (pinfunction "1_1") (pintype "passive"))
    )
    (net (code "38") (name "Net-(R1_EP_DR-Pad1)") (class "Default")
      (node (ref "R1_EP_DR") (pin "1") (pinfunction "1_1") (pintype "bidirectional"))
      (node (ref "R_TYPE_SEL") (pin "2") (pinfunction "2_2") (pintype "bidirectional"))
      (node (ref "SJ1") (pin "2") (pinfunction "2_2") (pintype "passive"))
    )
    (net (code "39") (name "Net-(U1-ANT)") (class "Default")
      (node (ref "C3") (pin "1") (pinfunction "1_1") (pintype "passive"))
      (node (ref "L1") (pin "1") (pinfunction "1_1") (pintype "passive"))
      (node (ref "U1") (pin "P$H23") (pinfunction "ANT_P$H23") (pintype "bidirectional"))
    )
    (net (code "40") (name "Net-(U1-DCC)") (class "Default")
      (node (ref "L2") (pin "1") (pinfunction "1_1") (pintype "passive"))
      (node (ref "U1") (pin "P$B3") (pinfunction "DCC_P$B3") (pintype "output"))
    )
    (net (code "41") (name "Net-(U1-DEC1)") (class "Default")
      (node (ref "C5") (pin "1") (pinfunction "1_1") (pintype "passive"))
      (node (ref "U1") (pin "P$C1") (pinfunction "DEC1_P$C1") (pintype "power_in"))
    )
    (net (code "42") (name "Net-(U1-DEC2)") (class "Default")
      (node (ref "C13") (pin "1") (pinfunction "1_1") (pintype "passive"))
      (node (ref "U1") (pin "P$A18") (pinfunction "DEC2_P$A18") (pintype "bidirectional"))
    )
    (net (code "43") (name "Net-(U1-DEC3)") (class "Default")
      (node (ref "C11") (pin "1") (pinfunction "1_1") (pintype "passive"))
      (node (ref "U1") (pin "P$D23") (pinfunction "DEC3_P$D23") (pintype "bidirectional"))
    )
    (net (code "44") (name "Net-(U1-DEC3V3)") (class "Default")
      (node (ref "C20") (pin "1") (pinfunction "1_1") (pintype "passive"))
      (node (ref "U1") (pin "P$AC5") (pinfunction "DEC3V3_P$AC5") (pintype "bidirectional"))
    )
    (net (code "45") (name "Net-(U1-DEC4)") (class "Default")
      (node (ref "C10") (pin "1") (pinfunction "1_1") (pintype "passive"))
      (node (ref "C15") (pin "1") (pinfunction "1_1") (pintype "passive"))
      (node (ref "C16") (pin "1") (pinfunction "1_1") (pintype "passive"))
      (node (ref "L3") (pin "2") (pinfunction "2_2") (pintype "passive"))
      (node (ref "U1") (pin "P$B5") (pinfunction "DEC4_P$B5") (pintype "power_in"))
      (node (ref "U1") (pin "P$E24") (pinfunction "DEC6_P$E24") (pintype "bidirectional"))
    )
    (net (code "46") (name "Net-(U1-DEC5)") (class "Default")
      (node (ref "C9") (pin "1") (pinfunction "1_1") (pintype "passive"))
      (node (ref "U1") (pin "P$N24") (pinfunction "DEC5_P$N24") (pintype "bidirectional"))
    )
    (net (code "47") (name "Net-(U1-P0.00{slash}XL1)") (class "Default")
      (node (ref "C17") (pin "2") (pinfunction "2_2") (pintype "passive"))
      (node (ref "U1") (pin "P$D2") (pinfunction "P0.00/XL1_P$D2") (pintype "bidirectional"))
      (node (ref "X2") (pin "1") (pinfunction "1_1") (pintype "passive"))
    )
    (net (code "48") (name "Net-(U1-P0.01{slash}XL2)") (class "Default")
      (node (ref "C18") (pin "2") (pinfunction "2_2") (pintype "passive"))
      (node (ref "U1") (pin "P$F2") (pinfunction "P0.01/XL2_P$F2") (pintype "bidirectional"))
      (node (ref "X2") (pin "2") (pinfunction "2_2") (pintype "passive"))
    )
    (net (code "49") (name "Net-(U1-XC1)") (class "Default")
      (node (ref "U1") (pin "P$B24") (pinfunction "XC1_P$B24") (pintype "input"))
      (node (ref "X1") (pin "1") (pinfunction "1_1") (pintype "passive"))
      (node (ref "XC1") (pin "1") (pinfunction "1_1") (pintype "passive"))
    )
    (net (code "50") (name "Net-(U1-XC2)") (class "Default")
      (node (ref "U1") (pin "P$A23") (pinfunction "XC2_P$A23") (pintype "output"))
      (node (ref "X1") (pin "3") (pinfunction "3_3") (pintype "passive"))
      (node (ref "XC2") (pin "1") (pinfunction "1_1") (pintype "passive"))
    )
    (net (code "51") (name "OUT+") (class "Default")
      (node (ref "IC4") (pin "A3") (pinfunction "OUT+_A3") (pintype "bidirectional"))
    )
    (net (code "52") (name "OUT-") (class "Default")
      (node (ref "IC4") (pin "C3") (pinfunction "OUT-_C3") (pintype "bidirectional"))
    )
    (net (code "53") (name "P0.04") (class "Default")
      (node (ref "U1") (pin "P$J1") (pinfunction "P0.04/AIN2_P$J1") (pintype "bidirectional"))
    )
    (net (code "54") (name "P0.13") (class "Default")
      (node (ref "C30") (pin "2") (pinfunction "2_2") (pintype "passive"))
      (node (ref "R5") (pin "1") (pinfunction "1_1") (pintype "bidirectional"))
      (node (ref "SW_UP") (pin "2") (pinfunction "2_2") (pintype "passive"))
      (node (ref "U1") (pin "P$AD8") (pinfunction "P0.13_P$AD8") (pintype "bidirectional"))
    )
    (net (code "55") (name "P0.14") (class "Default")
      (node (ref "C31") (pin "2") (pinfunction "2_2") (pintype "passive"))
      (node (ref "R8") (pin "1") (pinfunction "1_1") (pintype "bidirectional"))
      (node (ref "SW_ENT") (pin "2") (pinfunction "2_2") (pintype "passive"))
      (node (ref "U1") (pin "P$AC9") (pinfunction "P0.14_P$AC9") (pintype "bidirectional"))
    )
    (net (code "56") (name "P0.19") (class "Default")
      (node (ref "U1") (pin "P$AC15") (pinfunction "P0.19_P$AC15") (pintype "bidirectional"))
    )
    (net (code "57") (name "P0.20") (class "Default")
      (node (ref "U1") (pin "P$AD16") (pinfunction "P0.20_P$AD16") (pintype "bidirectional"))
    )
    (net (code "58") (name "P0.21") (class "Default")
      (node (ref "U1") (pin "P$AC17") (pinfunction "P0.21_P$AC17") (pintype "bidirectional"))
    )
    (net (code "59") (name "P0.22") (class "Default")
      (node (ref "U1") (pin "P$AD18") (pinfunction "P0.22_P$AD18") (pintype "bidirectional"))
    )
    (net (code "60") (name "P0.23") (class "Default")
      (node (ref "U1") (pin "P$AC19") (pinfunction "P0.23_P$AC19") (pintype "bidirectional"))
    )
    (net (code "61") (name "P0.24") (class "Default")
      (node (ref "U1") (pin "P$AD20") (pinfunction "P0.24_P$AD20") (pintype "bidirectional"))
    )
    (net (code "62") (name "P0.25") (class "Default")
      (node (ref "U1") (pin "P$AC21") (pinfunction "P0.25_P$AC21") (pintype "bidirectional"))
    )
    (net (code "63") (name "P0.26") (class "Default")
      (node (ref "U1") (pin "P$G1") (pinfunction "P0.26_P$G1") (pintype "bidirectional"))
    )
    (net (code "64") (name "P0.27") (class "Default")
      (node (ref "U1") (pin "P$H2") (pinfunction "P0.27_P$H2") (pintype "bidirectional"))
    )
    (net (code "65") (name "P0.28") (class "Default")
      (node (ref "U1") (pin "P$B11") (pinfunction "P0.28/AIN4_P$B11") (pintype "bidirectional"))
    )
    (net (code "66") (name "P0.29") (class "Default")
      (node (ref "U1") (pin "P$A10") (pinfunction "P0.29/AIN5_P$A10") (pintype "bidirectional"))
    )
    (net (code "67") (name "P0.30") (class "Default")
      (node (ref "U1") (pin "P$B9") (pinfunction "P0.30/AIN6_P$B9") (pintype "bidirectional"))
    )
    (net (code "68") (name "P0.31") (class "Default")
      (node (ref "U1") (pin "P$A8") (pinfunction "P0.31/AIN7_P$A8") (pintype "bidirectional"))
    )
    (net (code "69") (name "P1.01") (class "Default")
      (node (ref "DMG2305UX-7") (pin "1") (pinfunction "G_1") (pintype "bidirectional"))
      (node (ref "R_PWR_EPD") (pin "1") (pinfunction "1_1") (pintype "bidirectional"))
      (node (ref "U1") (pin "P$Y23") (pinfunction "P1.01_P$Y23") (pintype "bidirectional"))
    )
    (net (code "70") (name "P1.02") (class "Default")
      (node (ref "C29") (pin "2") (pinfunction "2_2") (pintype "passive"))
      (node (ref "R7") (pin "1") (pinfunction "1_1") (pintype "bidirectional"))
      (node (ref "SW_DN") (pin "2") (pinfunction "2_2") (pintype "passive"))
      (node (ref "U1") (pin "P$W24") (pinfunction "P1.02_P$W24") (pintype "bidirectional"))
    )
    (net (code "71") (name "P1.03") (class "Default")
      (node (ref "U1") (pin "P$V23") (pinfunction "P1.03_P$V23") (pintype "bidirectional"))
    )
    (net (code "72") (name "P1.04") (class "Default")
      (node (ref "U1") (pin "P$U24") (pinfunction "P1.04_P$U24") (pintype "bidirectional"))
    )
    (net (code "73") (name "P1.05") (class "Default")
      (node (ref "U1") (pin "P$T23") (pinfunction "P1.05_P$T23") (pintype "bidirectional"))
    )
    (net (code "74") (name "P1.06") (class "Default")
      (node (ref "U1") (pin "P$R24") (pinfunction "P1.06_P$R24") (pintype "bidirectional"))
    )
    (net (code "75") (name "P1.07") (class "Default")
      (node (ref "U1") (pin "P$P23") (pinfunction "P1.07_P$P23") (pintype "bidirectional"))
    )
    (net (code "76") (name "P1.09") (class "Default")
      (node (ref "U1") (pin "P$L24") (pinfunction "P0.09/NFC1_P$L24") (pintype "bidirectional"))
      (node (ref "U1") (pin "P$R1") (pinfunction "P1.09_P$R1") (pintype "bidirectional"))
    )
    (net (code "77") (name "P1.10") (class "Default")
      (node (ref "U1") (pin "P$A20") (pinfunction "P1.10_P$A20") (pintype "bidirectional"))
    )
    (net (code "78") (name "P1.11") (class "Default")
      (node (ref "U1") (pin "P$B19") (pinfunction "P1.11_P$B19") (pintype "bidirectional"))
    )
    (net (code "79") (name "P1.12") (class "Default")
      (node (ref "U1") (pin "P$B17") (pinfunction "P1.12_P$B17") (pintype "bidirectional"))
    )
    (net (code "80") (name "P1.13") (class "Default")
      (node (ref "U1") (pin "P$A16") (pinfunction "P1.13_P$A16") (pintype "bidirectional"))
    )
    (net (code "81") (name "P1.14") (class "Default")
      (node (ref "U1") (pin "P$B15") (pinfunction "P1.14_P$B15") (pintype "bidirectional"))
    )
    (net (code "82") (name "P1.15") (class "Default")
      (node (ref "U1") (pin "P$A14") (pinfunction "P1.15_P$A14") (pintype "bidirectional"))
    )
    (net (code "83") (name "PMIC_INT") (class "Default")
      (node (ref "IC1") (pin "A1") (pinfunction "~{INT}_A1") (pintype "bidirectional"))
      (node (ref "U1") (pin "P$T2") (pinfunction "P0.11_P$T2") (pintype "bidirectional"))
    )
    (net (code "84") (name "PREGVH") (class "Default")
      (node (ref "D5") (pin "1") (pinfunction "K_1") (pintype "bidirectional"))
      (node (ref "EPD_C9") (pin "2") (pinfunction "2_2") (pintype "passive"))
      (node (ref "J1") (pin "21") (pinfunction "21_21") (pintype "bidirectional"))
    )
    (net (code "85") (name "PREVGL") (class "Default")
      (node (ref "D2") (pin "2") (pinfunction "A_2") (pintype "bidirectional"))
      (node (ref "EPD_C11") (pin "2") (pinfunction "2_2") (pintype "passive"))
      (node (ref "J1") (pin "23") (pinfunction "23_23") (pintype "bidirectional"))
    )
    (net (code "86") (name "RESE") (class "Default")
      (node (ref "J1") (pin "3") (pinfunction "3_3") (pintype "bidirectional"))
      (node (ref "Q1") (pin "2") (pinfunction "S_2") (pintype "bidirectional"))
      (node (ref "R1_EP_DR") (pin "2") (pinfunction "2_2") (pintype "bidirectional"))
    )
    (net (code "87") (name "RESET") (class "Default")
      (node (ref "J2") (pin "6") (pinfunction "6_6") (pintype "bidirectional"))
      (node (ref "TP_RESET") (pin "TP") (pinfunction "TP_TP") (pintype "input"))
      (node (ref "U1") (pin "P$AC13") (pinfunction "P0.18/RESET_P$AC13") (pintype "bidirectional"))
    )
    (net (code "88") (name "SCK") (class "Default")
      (node (ref "J1") (pin "13") (pinfunction "13_13") (pintype "bidirectional"))
      (node (ref "U1") (pin "P$A12") (pinfunction "P0.02/AIN0_P$A12") (pintype "bidirectional"))
    )
    (net (code "89") (name "SCL") (class "Default")
      (node (ref "IC1") (pin "B1") (pinfunction "SCL_B1") (pintype "bidirectional"))
      (node (ref "IC3") (pin "12") (pinfunction "SCX_12") (pintype "bidirectional"))
      (node (ref "IC4") (pin "C1") (pinfunction "SCL_C1") (pintype "bidirectional"))
      (node (ref "R17") (pin "2") (pinfunction "2_2") (pintype "bidirectional"))
      (node (ref "R4") (pin "1") (pinfunction "1_1") (pintype "bidirectional"))
      (node (ref "TP_SCL") (pin "TP") (pinfunction "TP_TP") (pintype "input"))
      (node (ref "U1") (pin "P$M2") (pinfunction "P0.07_P$M2") (pintype "bidirectional"))
      (node (ref "U3") (pin "7") (pinfunction "SCL_7") (pintype "input"))
    )
    (net (code "90") (name "SDA") (class "Default")
      (node (ref "IC1") (pin "C1") (pinfunction "SDA_C1") (pintype "bidirectional"))
      (node (ref "IC3") (pin "2") (pinfunction "SDX_2") (pintype "bidirectional"))
      (node (ref "IC4") (pin "B2") (pinfunction "SDA_B2") (pintype "bidirectional"))
      (node (ref "R18") (pin "2") (pinfunction "2_2") (pintype "bidirectional"))
      (node (ref "R2") (pin "1") (pinfunction "1_1") (pintype "bidirectional"))
      (node (ref "TP_SDA") (pin "TP") (pinfunction "TP_TP") (pintype "input"))
      (node (ref "U1") (pin "P$L1") (pinfunction "P0.06_P$L1") (pintype "bidirectional"))
      (node (ref "U3") (pin "8") (pinfunction "SDA_8") (pintype "bidirectional"))
    )
    (net (code "91") (name "SWDCLK") (class "Default")
      (node (ref "J2") (pin "4") (pinfunction "4_4") (pintype "bidirectional"))
      (node (ref "TP_SWDCLK") (pin "TP") (pinfunction "TP_TP") (pintype "input"))
      (node (ref "U1") (pin "P$AA24") (pinfunction "SWDCLK_P$AA24") (pintype "input"))
    )
    (net (code "92") (name "SWDIO") (class "Default")
      (node (ref "J2") (pin "2") (pinfunction "2_2") (pintype "bidirectional"))
      (node (ref "TP_SWDIO") (pin "TP") (pinfunction "TP_TP") (pintype "input"))
      (node (ref "U1") (pin "P$AC24") (pinfunction "SWDIO_P$AC24") (pintype "bidirectional"))
    )
    (net (code "93") (name "SWO") (class "Default")
      (node (ref "TP_SWO") (pin "TP") (pinfunction "TP_TP") (pintype "input"))
      (node (ref "U1") (pin "P$AD22") (pinfunction "P1.00_P$AD22") (pintype "bidirectional"))
    )
    (net (code "94") (name "VBAT") (class "Default")
      (node (ref "C27") (pin "2") (pinfunction "2_2") (pintype "passive"))
      (node (ref "C37") (pin "2") (pinfunction "2_2") (pintype "passive"))
      (node (ref "IC1") (pin "C2") (pinfunction "BAT_C2") (pintype "bidirectional"))
      (node (ref "TP_VBAT") (pin "TP") (pinfunction "TP_TP") (pintype "input"))
      (node (ref "U3") (pin "2") (pinfunction "CELL_2") (pintype "power_in"))
      (node (ref "U3") (pin "3") (pinfunction "VDD_3") (pintype "power_in"))
    )
    (net (code "95") (name "VBUS") (class "Default")
      (node (ref "C21") (pin "1") (pinfunction "1_1") (pintype "passive"))
      (node (ref "C38") (pin "2") (pinfunction "2_2") (pintype "passive"))
      (node (ref "C42") (pin "1") (pinfunction "1_1") (pintype "passive"))
      (node (ref "C43") (pin "1") (pinfunction "1_1") (pintype "passive"))
      (node (ref "D3") (pin "5") (pinfunction "VBUS_5") (pintype "bidirectional"))
      (node (ref "IC1") (pin "A2") (pinfunction "IN_A2") (pintype "bidirectional"))
      (node (ref "J4") (pin "A4_B9") (pinfunction "VBUS_A4_B9") (pintype "power_in"))
      (node (ref "J4") (pin "A9_B4") (pinfunction "VBUS_A9_B4") (pintype "power_in"))
      (node (ref "U1") (pin "P$AD2") (pinfunction "VBUS_P$AD2") (pintype "power_in"))
    )
    (net (code "96") (name "VREG") (class "Default")
      (node (ref "C23") (pin "2") (pinfunction "2_2") (pintype "passive"))
      (node (ref "C24") (pin "2") (pinfunction "2_2") (pintype "passive"))
      (node (ref "C39") (pin "1") (pinfunction "1_1") (pintype "passive"))
      (node (ref "IC1") (pin "B2") (pinfunction "SYS_B2") (pintype "bidirectional"))
      (node (ref "IC2") (pin "A1") (pinfunction "EN_A1") (pintype "bidirectional"))
      (node (ref "IC2") (pin "A2") (pinfunction "VIN_1_A2") (pintype "bidirectional"))
      (node (ref "IC2") (pin "A3") (pinfunction "VIN_2_A3") (pintype "bidirectional"))
      (node (ref "TP_VREG") (pin "TP") (pinfunction "TP_TP") (pintype "input"))
    )
    (net (code "97") (name "unconnected-(ANT1-NC-Pad2)") (class "Default")
      (node (ref "ANT1") (pin "2") (pinfunction "NC_2") (pintype "no_connect"))
    )
    (net (code "98") (name "unconnected-(IC3-ASCL-Pad11)") (class "Default")
      (node (ref "IC3") (pin "11") (pinfunction "ASCL_11") (pintype "bidirectional"))
    )
    (net (code "99") (name "unconnected-(IC3-ASDA-Pad4)") (class "Default")
      (node (ref "IC3") (pin "4") (pinfunction "ASDA_4") (pintype "bidirectional"))
    )
    (net (code "100") (name "unconnected-(J1-Pad1)") (class "Default")
      (node (ref "J1") (pin "1") (pinfunction "1_1") (pintype "bidirectional"))
    )
    (net (code "101") (name "unconnected-(J1-Pad6)") (class "Default")
      (node (ref "J1") (pin "6") (pinfunction "6_6") (pintype "bidirectional"))
    )
    (net (code "102") (name "unconnected-(J1-Pad7)") (class "Default")
      (node (ref "J1") (pin "7") (pinfunction "7_7") (pintype "bidirectional"))
    )
    (net (code "103") (name "unconnected-(J4-SBU1-PadA8)") (class "Default")
      (node (ref "J4") (pin "A8") (pinfunction "SBU1_A8") (pintype "bidirectional"))
    )
    (net (code "104") (name "unconnected-(J4-SBU2-PadB8)") (class "Default")
      (node (ref "J4") (pin "B8") (pinfunction "SBU2_B8") (pintype "bidirectional"))
    )
    (net (code "105") (name "unconnected-(U1-DCCH-PadP$AB2)") (class "Default")
      (node (ref "U1") (pin "P$AB2") (pinfunction "DCCH_P$AB2") (pintype "bidirectional"))
    )
  )
)
